# MCPICKUP.net
KiCad netlist of a schematic drawn in EasyEDA
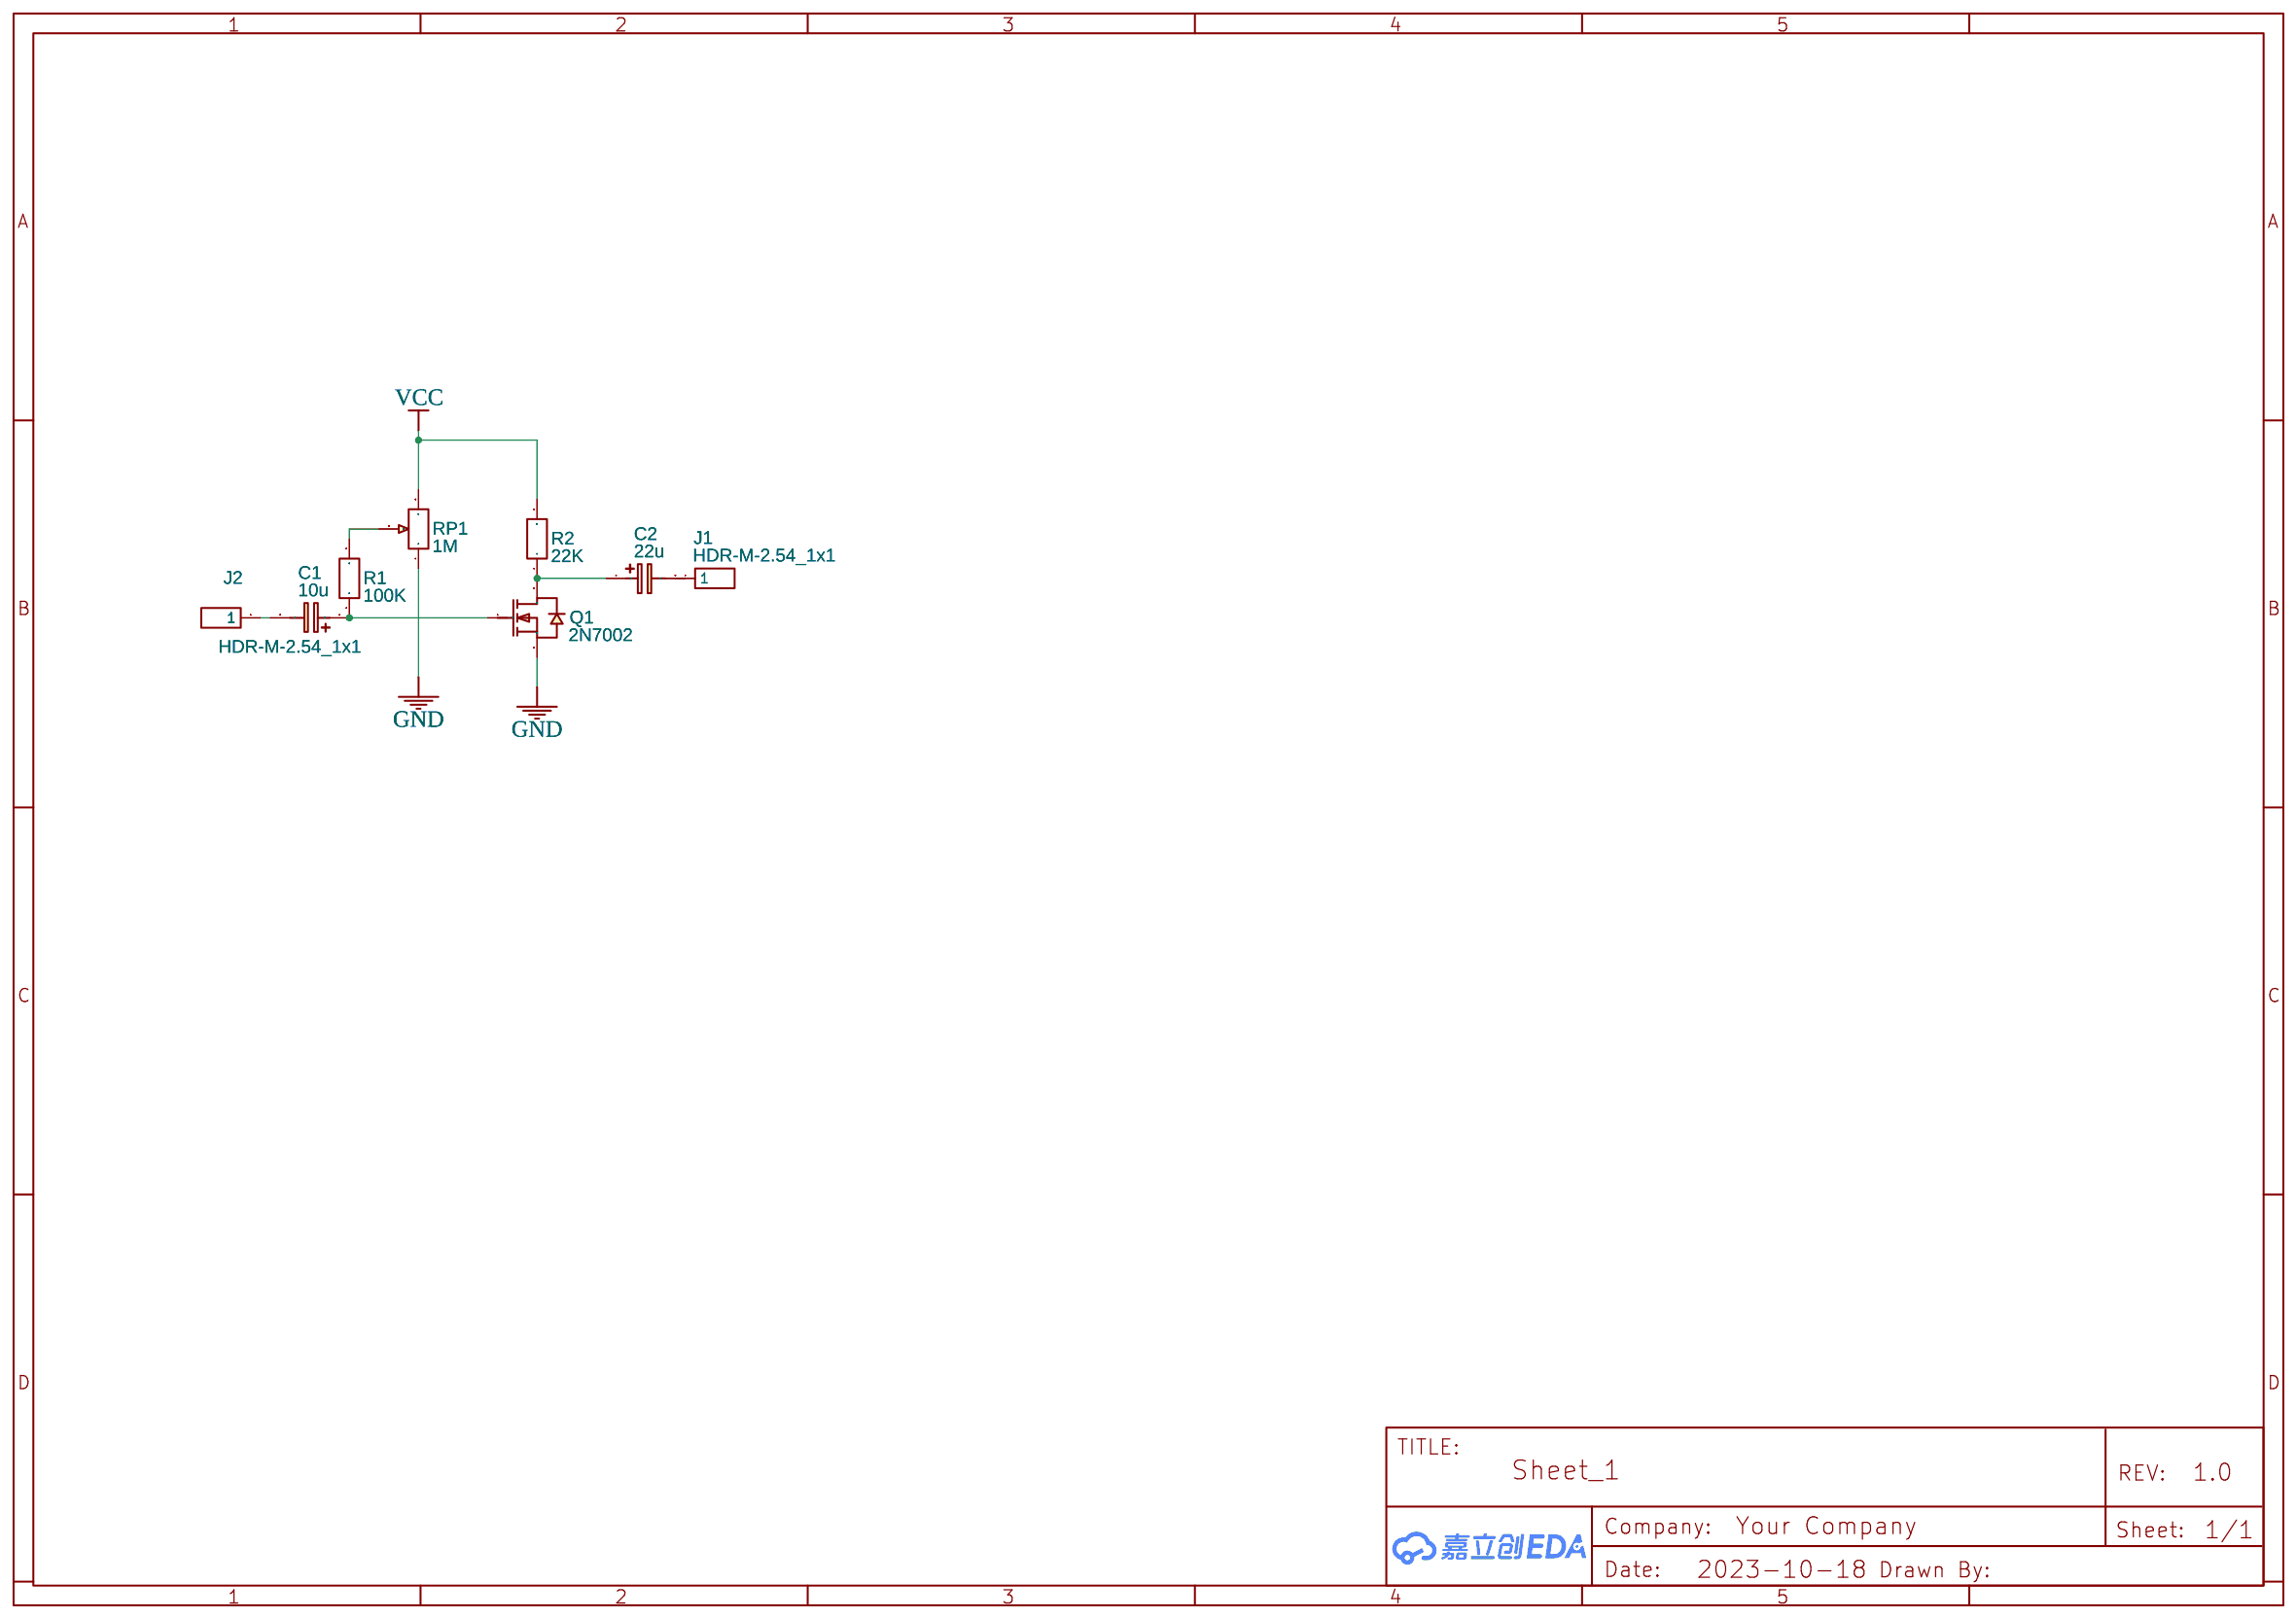
[diagram p0: schematic sheet]

(export (version "E")
  (design (tool "Eeschema 10.0.6"))
  (components
    (comp (ref "C1") (value "10u") (libsource (lib "") (part "C_Tan_SMD_A_EU_1")))
    (comp (ref "C2") (value "22u") (libsource (lib "") (part "C_Tan_SMD_A_EU")))
    (comp (ref "J1")
      (value "HDR-M-2.54_1x1")
      (fields (field (name "BOM_Supplier Part") "C81276"))
      (libsource (lib "") (part "HDR-M-2.54_1x1"))
    )
    (comp (ref "J2")
      (value "HDR-M-2.54_1x1")
      (fields (field (name "BOM_Supplier Part") "C81276"))
      (libsource (lib "") (part "HDR-M-2.54_1x1_1"))
    )
    (comp (ref "Q1")
      (value "2N7002")
      (fields (field (name "BOM_Manufacturer Part") "2N7002,215") (field (name "BOM_Supplier Part") "C65189"))
      (libsource (lib "") (part "2N7002"))
    )
    (comp (ref "R1") (value "100K") (libsource (lib "") (part "R_0603_EU")))
    (comp (ref "R2") (value "22K") (libsource (lib "") (part "R_0603_EU")))
    (comp (ref "RP1") (value "1M") (libsource (lib "") (part "R_3296W_EU")))
  )
  (nets
    (net (code "1") (name "GND") (class "Default")
      (node (ref "Q1") (pin "2") (pinfunction "S_2") (pintype "unspecified"))
      (node (ref "RP1") (pin "1") (pinfunction "1_1") (pintype "input"))
    )
    (net (code "2") (name "Net-(C1-Pad2)") (class "Default")
      (node (ref "C1") (pin "2") (pinfunction "2_2") (pintype "unspecified"))
      (node (ref "J2") (pin "1") (pinfunction "1_1") (pintype "input"))
    )
    (net (code "3") (name "Net-(Q1-D)") (class "Default")
      (node (ref "C2") (pin "1") (pinfunction "1_1") (pintype "unspecified"))
      (node (ref "Q1") (pin "3") (pinfunction "D_3") (pintype "unspecified"))
      (node (ref "R2") (pin "1") (pinfunction "1_1") (pintype "unspecified"))
    )
    (net (code "4") (name "Net-(Q1-G)") (class "Default")
      (node (ref "C1") (pin "1") (pinfunction "1_1") (pintype "unspecified"))
      (node (ref "Q1") (pin "1") (pinfunction "G_1") (pintype "unspecified"))
      (node (ref "R1") (pin "1") (pinfunction "1_1") (pintype "unspecified"))
    )
    (net (code "5") (name "Net-(R1-Pad2)") (class "Default")
      (node (ref "R1") (pin "2") (pinfunction "2_2") (pintype "unspecified"))
      (node (ref "RP1") (pin "2") (pinfunction "2_2") (pintype "input"))
    )
    (net (code "6") (name "VCC") (class "Default")
      (node (ref "R2") (pin "2") (pinfunction "2_2") (pintype "unspecified"))
      (node (ref "RP1") (pin "3") (pinfunction "3_3") (pintype "input"))
    )
    (net (code "7") (name "unconnected-(C2-Pad2)") (class "Default")
      (node (ref "C2") (pin "2") (pinfunction "2_2") (pintype "unspecified"))
    )
    (net (code "8") (name "unconnected-(J1-Pad1)") (class "Default")
      (node (ref "J1") (pin "1") (pinfunction "1_1") (pintype "input"))
    )
  )
)
